# BladeCore-M40.net
KiCad netlist of a schematic drawn in EAGLE
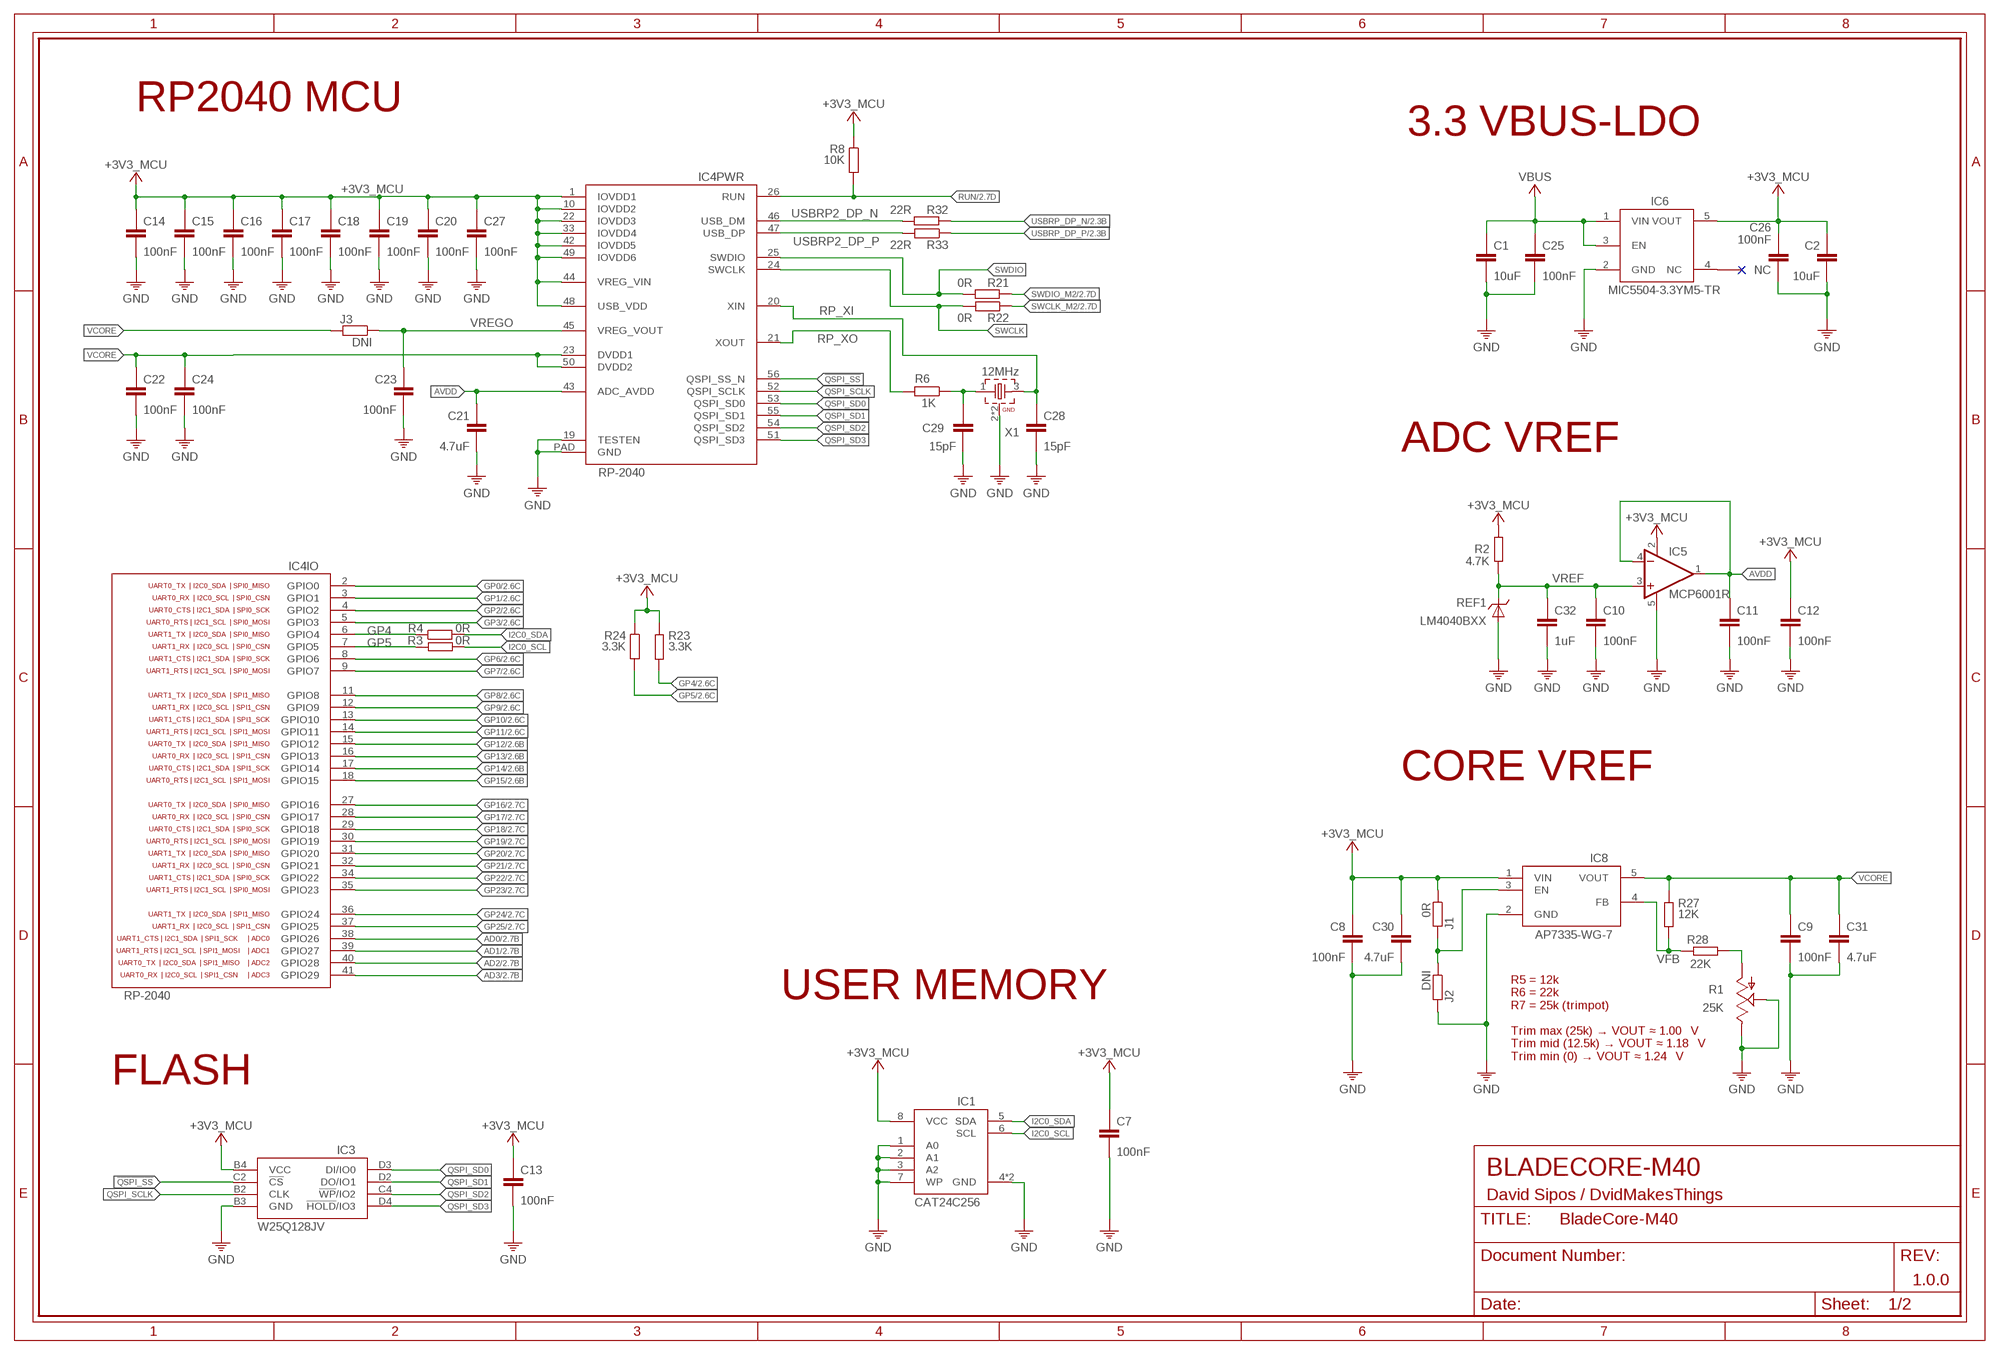
[diagram p0: schematic, sheet 1]
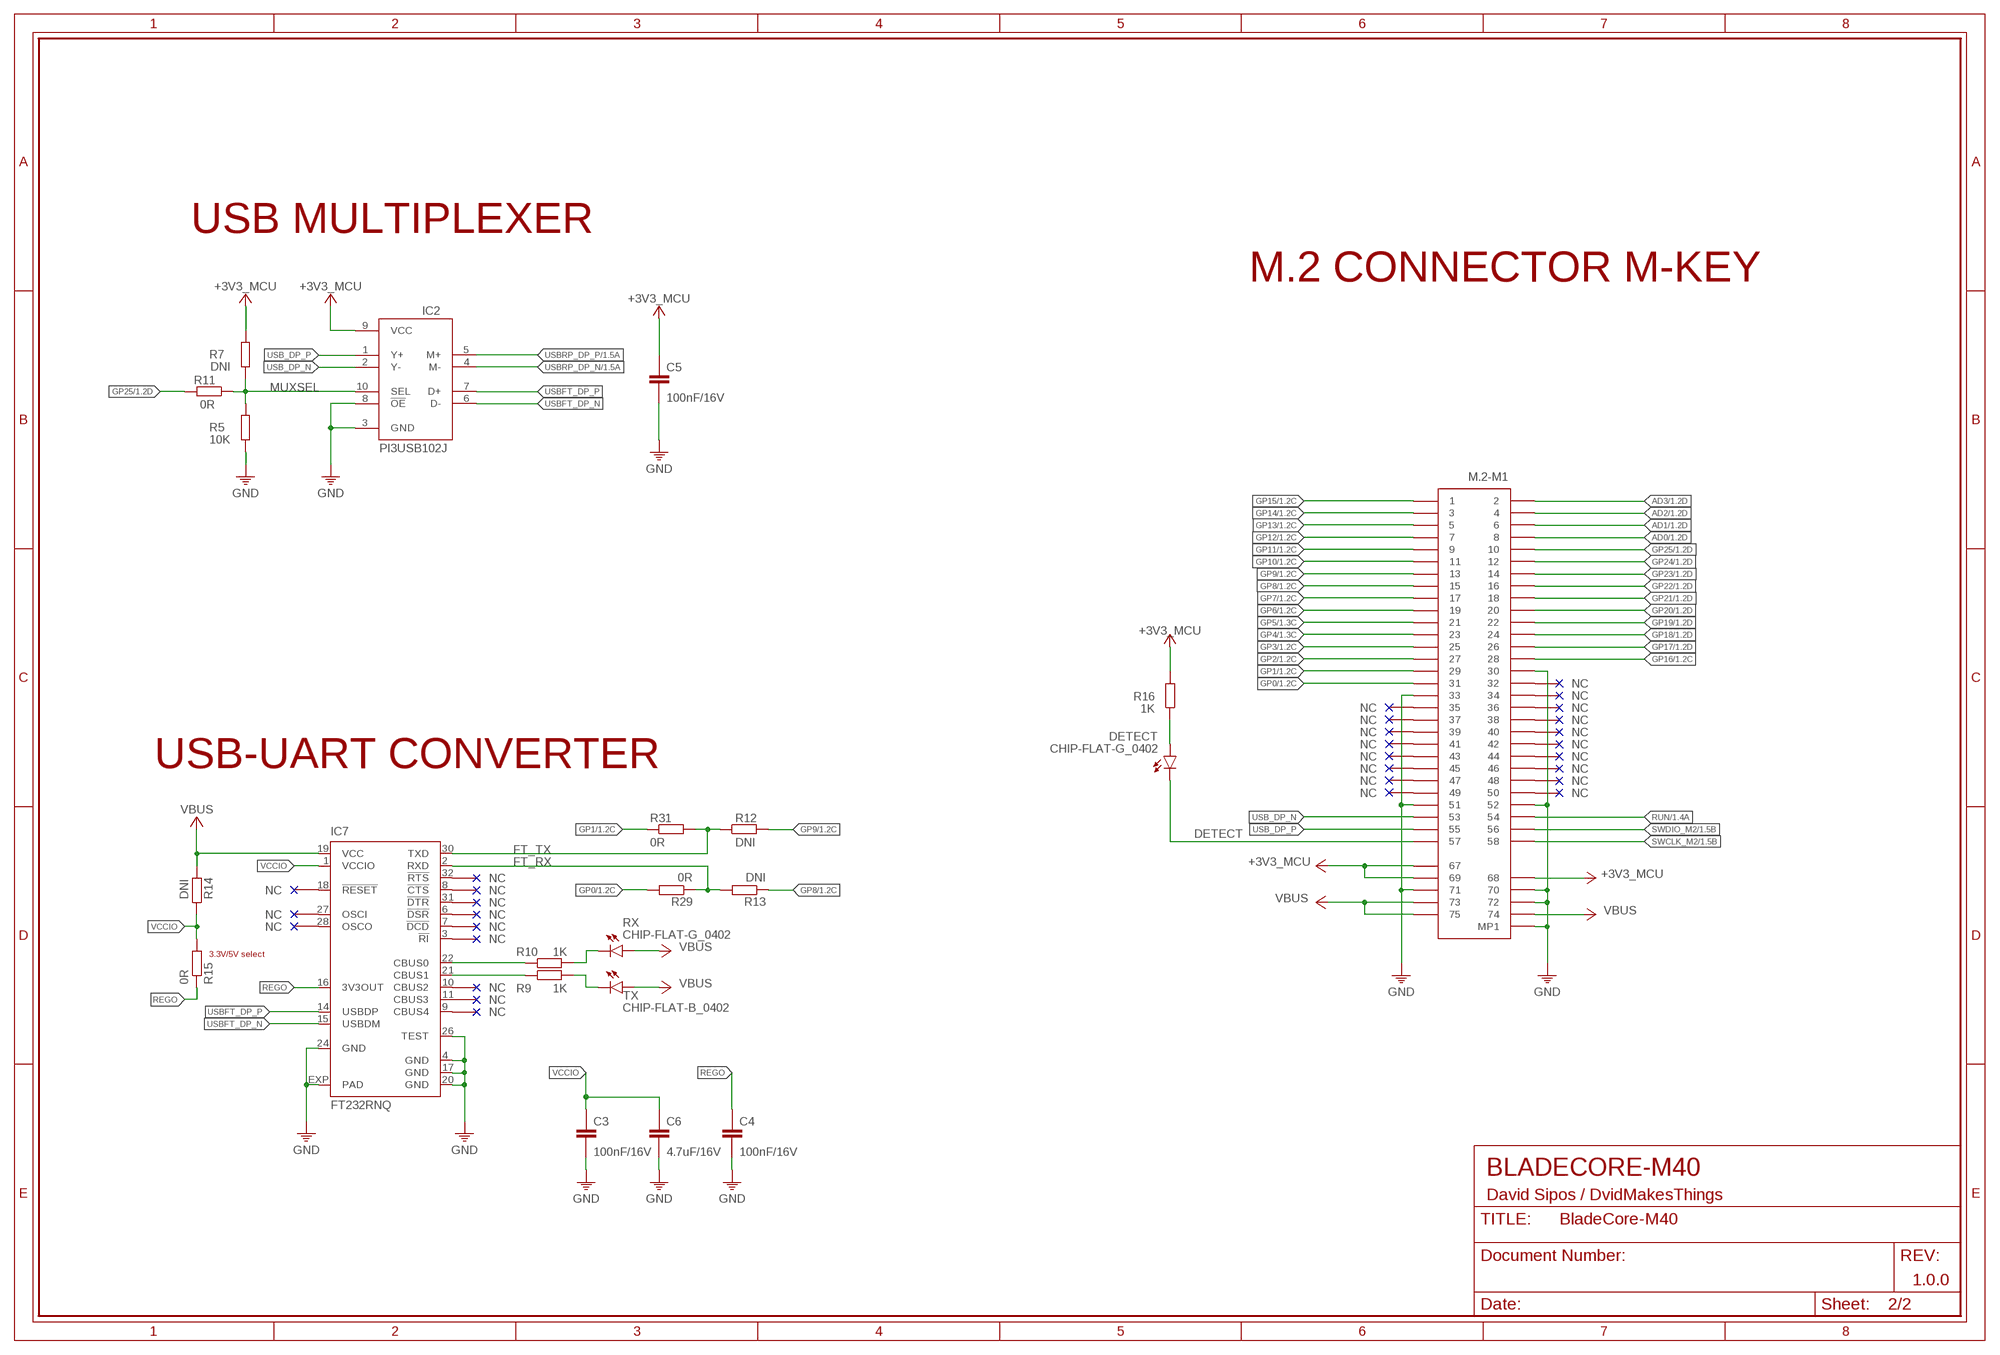
[diagram p1: schematic, sheet 2]

(export (version "E")
  (design (tool "Eeschema 10.0.6"))
  (components
    (comp (ref "C3")
      (value "100nF/16V")
      (footprint "eagle-import:0201")
      (libsource (lib "eagle-import") (part "C-0201"))
    )
    (comp (ref "C4")
      (value "100nF/16V")
      (footprint "eagle-import:0201")
      (libsource (lib "eagle-import") (part "C-0201"))
    )
    (comp (ref "C5")
      (value "100nF/16V")
      (footprint "eagle-import:0201")
      (libsource (lib "eagle-import") (part "C-0201"))
    )
    (comp (ref "C6")
      (value "4.7uF/16V")
      (footprint "eagle-import:0201")
      (libsource (lib "eagle-import") (part "C-0201"))
    )
    (comp (ref "DETECT")
      (value "CHIP-FLAT-G_0402")
      (footprint "eagle-import:LEDC1005X25N_FLAT-G")
      (libsource (lib "eagle-import") (part "CHIP-FLAT-G_0402"))
    )
    (comp (ref "IC2")
      (value "PI3USB102J")
      (footprint "eagle-import:QFN40P120X140X35-10N")
      (libsource (lib "eagle-import") (part "PI3USB102JXUCEX"))
    )
    (comp (ref "IC7")
      (value "FT232RNQ")
      (footprint "eagle-import:QFN32")
      (libsource (lib "eagle-import") (part "FT232RQ"))
    )
    (comp (ref "M.2-M1")
      (value "M.2-M-KEY")
      (footprint "eagle-import:M.2-M-KEY")
      (libsource (lib "eagle-import") (part "M.2-M-KEY"))
    )
    (comp (ref "R5")
      (value "10K")
      (footprint "eagle-import:R0201")
      (libsource (lib "eagle-import") (part "R0201"))
    )
    (comp (ref "R7")
      (value "DNI")
      (footprint "eagle-import:R0201")
      (libsource (lib "eagle-import") (part "R0201"))
    )
    (comp (ref "R9")
      (value "1K")
      (footprint "eagle-import:R0201")
      (libsource (lib "eagle-import") (part "R0201"))
    )
    (comp (ref "R10")
      (value "1K")
      (footprint "eagle-import:R0201")
      (libsource (lib "eagle-import") (part "R0201"))
    )
    (comp (ref "R11")
      (value "0R")
      (footprint "eagle-import:R0201")
      (libsource (lib "eagle-import") (part "R0201"))
    )
    (comp (ref "R12")
      (value "DNI")
      (footprint "eagle-import:R0201")
      (libsource (lib "eagle-import") (part "R0201"))
    )
    (comp (ref "R13")
      (value "DNI")
      (footprint "eagle-import:R0201")
      (libsource (lib "eagle-import") (part "R0201"))
    )
    (comp (ref "R14")
      (value "DNI")
      (footprint "eagle-import:R0201")
      (libsource (lib "eagle-import") (part "R0201"))
    )
    (comp (ref "R15")
      (value "0R")
      (footprint "eagle-import:R0201")
      (libsource (lib "eagle-import") (part "R0201"))
    )
    (comp (ref "R16")
      (value "1K")
      (footprint "eagle-import:R0201")
      (libsource (lib "eagle-import") (part "R0201"))
    )
    (comp (ref "R29")
      (value "0R")
      (footprint "eagle-import:R0201")
      (libsource (lib "eagle-import") (part "R0201"))
    )
    (comp (ref "R31")
      (value "0R")
      (footprint "eagle-import:R0201")
      (libsource (lib "eagle-import") (part "R0201"))
    )
    (comp (ref "RX")
      (value "CHIP-FLAT-G_0402")
      (footprint "eagle-import:LEDC1005X25N_FLAT-G")
      (libsource (lib "eagle-import") (part "CHIP-FLAT-G_0402"))
    )
    (comp (ref "TX")
      (value "CHIP-FLAT-B_0402")
      (footprint "eagle-import:LEDC1005X25N_FLAT-B")
      (libsource (lib "eagle-import") (part "CHIP-FLAT-B_0402"))
    )
    (comp (ref "C1")
      (value "10uF")
      (footprint "eagle-import:0805")
      (libsource (lib "eagle-import") (part "C0805"))
    )
    (comp (ref "C2")
      (value "10uF")
      (footprint "eagle-import:0805")
      (libsource (lib "eagle-import") (part "C0805"))
    )
    (comp (ref "C7")
      (value "100nF")
      (footprint "eagle-import:0201")
      (libsource (lib "eagle-import") (part "C-0201"))
    )
    (comp (ref "C8")
      (value "100nF")
      (footprint "eagle-import:0201")
      (libsource (lib "eagle-import") (part "C-0201"))
    )
    (comp (ref "C9")
      (value "100nF")
      (footprint "eagle-import:0201")
      (libsource (lib "eagle-import") (part "C-0201"))
    )
    (comp (ref "C10")
      (value "100nF")
      (footprint "eagle-import:0201")
      (libsource (lib "eagle-import") (part "C-0201"))
    )
    (comp (ref "C11")
      (value "100nF")
      (footprint "eagle-import:0201")
      (libsource (lib "eagle-import") (part "C-0201"))
    )
    (comp (ref "C12")
      (value "100nF")
      (footprint "eagle-import:0201")
      (libsource (lib "eagle-import") (part "C-0201"))
    )
    (comp (ref "C13")
      (value "100nF")
      (footprint "eagle-import:0201")
      (libsource (lib "eagle-import") (part "C-0201"))
    )
    (comp (ref "C14")
      (value "100nF")
      (footprint "eagle-import:0201")
      (libsource (lib "eagle-import") (part "C-0201"))
    )
    (comp (ref "C15")
      (value "100nF")
      (footprint "eagle-import:0201")
      (libsource (lib "eagle-import") (part "C-0201"))
    )
    (comp (ref "C16")
      (value "100nF")
      (footprint "eagle-import:0201")
      (libsource (lib "eagle-import") (part "C-0201"))
    )
    (comp (ref "C17")
      (value "100nF")
      (footprint "eagle-import:0201")
      (libsource (lib "eagle-import") (part "C-0201"))
    )
    (comp (ref "C18")
      (value "100nF")
      (footprint "eagle-import:0201")
      (libsource (lib "eagle-import") (part "C-0201"))
    )
    (comp (ref "C19")
      (value "100nF")
      (footprint "eagle-import:0201")
      (libsource (lib "eagle-import") (part "C-0201"))
    )
    (comp (ref "C20")
      (value "100nF")
      (footprint "eagle-import:0201")
      (libsource (lib "eagle-import") (part "C-0201"))
    )
    (comp (ref "C21")
      (value "4.7uF")
      (footprint "eagle-import:C0402")
      (libsource (lib "eagle-import") (part "C-0402"))
    )
    (comp (ref "C22")
      (value "100nF")
      (footprint "eagle-import:0201")
      (libsource (lib "eagle-import") (part "C-0201"))
    )
    (comp (ref "C23")
      (value "100nF")
      (footprint "eagle-import:0201")
      (libsource (lib "eagle-import") (part "C-0201"))
    )
    (comp (ref "C24")
      (value "100nF")
      (footprint "eagle-import:0201")
      (libsource (lib "eagle-import") (part "C-0201"))
    )
    (comp (ref "C25")
      (value "100nF")
      (footprint "eagle-import:0201")
      (libsource (lib "eagle-import") (part "C-0201"))
    )
    (comp (ref "C26")
      (value "100nF")
      (footprint "eagle-import:0201")
      (libsource (lib "eagle-import") (part "C-0201"))
    )
    (comp (ref "C27")
      (value "100nF")
      (footprint "eagle-import:0201")
      (libsource (lib "eagle-import") (part "C-0201"))
    )
    (comp (ref "C28")
      (value "15pF")
      (footprint "eagle-import:0201")
      (libsource (lib "eagle-import") (part "C-0201"))
    )
    (comp (ref "C29")
      (value "15pF")
      (footprint "eagle-import:0201")
      (libsource (lib "eagle-import") (part "C-0201"))
    )
    (comp (ref "C30")
      (value "4.7uF")
      (footprint "eagle-import:C0402")
      (libsource (lib "eagle-import") (part "C-0402"))
    )
    (comp (ref "C31")
      (value "4.7uF")
      (footprint "eagle-import:C0402")
      (libsource (lib "eagle-import") (part "C-0402"))
    )
    (comp (ref "C32")
      (value "1uF")
      (footprint "eagle-import:C0402")
      (libsource (lib "eagle-import") (part "C-0402"))
    )
    (comp (ref "IC1")
      (value "CAT24C512HU5IGT3")
      (footprint "eagle-import:SON50P300X200X50-9T130X140N")
      (libsource (lib "eagle-import") (part "CAT24C256-HU4"))
    )
    (comp (ref "IC3")
      (value "W25Q128JVCIQ TR")
      (footprint "eagle-import:BGA24C100P4X6_800X600X120N")
      (libsource (lib "eagle-import") (part "W25Q128JVC"))
    )
    (comp (ref "IC4")
      (value "RP-2040")
      (footprint "eagle-import:QFN56")
      (libsource (lib "eagle-import") (part "RP-2040"))
    )
    (comp (ref "IC5")
      (value "MCP6001R")
      (footprint "eagle-import:SOT23-5")
      (libsource (lib "eagle-import") (part "MCP6001RT"))
    )
    (comp (ref "IC6")
      (value "MIC5504-3.3YM5-TR")
      (footprint "eagle-import:SOT23-5")
      (libsource (lib "eagle-import") (part "MIC5504-3.3YM5-TR"))
    )
    (comp (ref "IC8")
      (value "AP7335-WG-7")
      (footprint "eagle-import:SOT23-5")
      (libsource (lib "eagle-import") (part "AP7335-WG-7"))
    )
    (comp (ref "J1")
      (value "0R")
      (footprint "eagle-import:R0201")
      (libsource (lib "eagle-import") (part "R0201"))
    )
    (comp (ref "J2")
      (value "DNI")
      (footprint "eagle-import:R0201")
      (libsource (lib "eagle-import") (part "R0201"))
    )
    (comp (ref "J3")
      (value "DNI")
      (footprint "eagle-import:R0201")
      (libsource (lib "eagle-import") (part "R0201"))
    )
    (comp (ref "R1")
      (value "25K")
      (footprint "eagle-import:SMD_TRIMMER")
      (fields
        (field (name "DIGIKEY_PART_NUMBER") "987-1694-2-ND")
        (field (name "MANUFACTURER") "TT Electronics/BI")
        (field (name "MPN") "35WR10KLFTR")
        (field (name "CREATED_BY") "PCBLayout.com")
      )
      (libsource (lib "eagle-import") (part "35WR10KLFTR"))
    )
    (comp (ref "R2")
      (value "4.7K")
      (footprint "eagle-import:R0201")
      (libsource (lib "eagle-import") (part "R0201"))
    )
    (comp (ref "R3")
      (value "0R")
      (footprint "eagle-import:R0201")
      (libsource (lib "eagle-import") (part "R0201"))
    )
    (comp (ref "R4")
      (value "0R")
      (footprint "eagle-import:R0201")
      (libsource (lib "eagle-import") (part "R0201"))
    )
    (comp (ref "R6")
      (value "1K")
      (footprint "eagle-import:R0201")
      (libsource (lib "eagle-import") (part "R0201"))
    )
    (comp (ref "R8")
      (value "10K")
      (footprint "eagle-import:R0201")
      (libsource (lib "eagle-import") (part "R0201"))
    )
    (comp (ref "R21")
      (value "0R")
      (footprint "eagle-import:R0201")
      (libsource (lib "eagle-import") (part "R0201"))
    )
    (comp (ref "R22")
      (value "0R")
      (footprint "eagle-import:R0201")
      (libsource (lib "eagle-import") (part "R0201"))
    )
    (comp (ref "R23")
      (value "3.3K")
      (footprint "eagle-import:R0201")
      (libsource (lib "eagle-import") (part "R0201"))
    )
    (comp (ref "R24")
      (value "3.3K")
      (footprint "eagle-import:R0201")
      (libsource (lib "eagle-import") (part "R0201"))
    )
    (comp (ref "R27")
      (value "12K")
      (footprint "eagle-import:R0201")
      (libsource (lib "eagle-import") (part "R0201"))
    )
    (comp (ref "R28")
      (value "22K")
      (footprint "eagle-import:R0201")
      (libsource (lib "eagle-import") (part "R0201"))
    )
    (comp (ref "R32")
      (value "22R")
      (footprint "eagle-import:R0201")
      (libsource (lib "eagle-import") (part "R0201"))
    )
    (comp (ref "R33")
      (value "22R")
      (footprint "eagle-import:R0201")
      (libsource (lib "eagle-import") (part "R0201"))
    )
    (comp (ref "REF1")
      (value "LM4040BXX")
      (footprint "eagle-import:SOT23")
      (libsource (lib "eagle-import") (part "LM4040BXX"))
    )
    (comp (ref "X1")
      (value "12MHz")
      (footprint "eagle-import:WE-XTAL_CFPX-180")
      (fields (field (name "TOLERANCE") "±20ppm"))
      (libsource (lib "eagle-import") (part "WE-XTAL_CFPX-180_830069944"))
    )
  )
  (nets
    (net (code "1") (name "+3V3_MCU") (class "Default")
      (node (ref "C12") (pin "1") (pinfunction "1_1") (pintype "passive"))
      (node (ref "C13") (pin "1") (pinfunction "1_1") (pintype "passive"))
      (node (ref "C14") (pin "1") (pinfunction "1_1") (pintype "passive"))
      (node (ref "C15") (pin "1") (pinfunction "1_1") (pintype "passive"))
      (node (ref "C16") (pin "1") (pinfunction "1_1") (pintype "passive"))
      (node (ref "C17") (pin "1") (pinfunction "1_1") (pintype "passive"))
      (node (ref "C18") (pin "1") (pinfunction "1_1") (pintype "passive"))
      (node (ref "C19") (pin "1") (pinfunction "1_1") (pintype "passive"))
      (node (ref "C2") (pin "1") (pinfunction "1_1") (pintype "passive"))
      (node (ref "C20") (pin "1") (pinfunction "1_1") (pintype "passive"))
      (node (ref "C26") (pin "1") (pinfunction "1_1") (pintype "passive"))
      (node (ref "C27") (pin "1") (pinfunction "1_1") (pintype "passive"))
      (node (ref "C30") (pin "1") (pinfunction "1_1") (pintype "passive"))
      (node (ref "C5") (pin "1") (pinfunction "1_1") (pintype "passive"))
      (node (ref "C7") (pin "1") (pinfunction "1_1") (pintype "passive"))
      (node (ref "C8") (pin "1") (pinfunction "1_1") (pintype "passive"))
      (node (ref "IC1") (pin "8") (pinfunction "VCC_8") (pintype "power_in"))
      (node (ref "IC2") (pin "9") (pinfunction "VCC_9") (pintype "power_in"))
      (node (ref "IC3") (pin "B4") (pinfunction "VCC_B4") (pintype "power_in"))
      (node (ref "IC4") (pin "1") (pinfunction "IOVDD1_1") (pintype "power_in"))
      (node (ref "IC4") (pin "10") (pinfunction "IOVDD2_10") (pintype "power_in"))
      (node (ref "IC4") (pin "22") (pinfunction "IOVDD3_22") (pintype "power_in"))
      (node (ref "IC4") (pin "33") (pinfunction "IOVDD4_33") (pintype "power_in"))
      (node (ref "IC4") (pin "42") (pinfunction "IOVDD5_42") (pintype "power_in"))
      (node (ref "IC4") (pin "44") (pinfunction "VREG_VIN_44") (pintype "power_in"))
      (node (ref "IC4") (pin "48") (pinfunction "USB_VDD_48") (pintype "power_in"))
      (node (ref "IC4") (pin "49") (pinfunction "IOVDD6_49") (pintype "power_in"))
      (node (ref "IC5") (pin "2") (pinfunction "V+_2") (pintype "power_in"))
      (node (ref "IC6") (pin "5") (pinfunction "VOUT_5") (pintype "bidirectional"))
      (node (ref "IC8") (pin "1") (pinfunction "VIN_1") (pintype "power_in"))
      (node (ref "J1") (pin "1") (pinfunction "1_1") (pintype "passive"))
      (node (ref "M.2-M1") (pin "P$67") (pinfunction "67_P$67") (pintype "bidirectional"))
      (node (ref "M.2-M1") (pin "P$68") (pinfunction "68_P$68") (pintype "bidirectional"))
      (node (ref "M.2-M1") (pin "P$69") (pinfunction "69_P$69") (pintype "bidirectional"))
      (node (ref "R16") (pin "2") (pinfunction "2_2") (pintype "passive"))
      (node (ref "R2") (pin "2") (pinfunction "2_2") (pintype "passive"))
      (node (ref "R23") (pin "1") (pinfunction "1_1") (pintype "passive"))
      (node (ref "R24") (pin "1") (pinfunction "1_1") (pintype "passive"))
      (node (ref "R7") (pin "2") (pinfunction "2_2") (pintype "passive"))
      (node (ref "R8") (pin "1") (pinfunction "1_1") (pintype "passive"))
    )
    (net (code "2") (name "AD0") (class "Default")
      (node (ref "IC4") (pin "38") (pinfunction "GPIO26_38") (pintype "bidirectional"))
      (node (ref "M.2-M1") (pin "P$8") (pinfunction "8_P$8") (pintype "bidirectional"))
    )
    (net (code "3") (name "AD1") (class "Default")
      (node (ref "IC4") (pin "39") (pinfunction "GPIO27_39") (pintype "bidirectional"))
      (node (ref "M.2-M1") (pin "P$6") (pinfunction "6_P$6") (pintype "bidirectional"))
    )
    (net (code "4") (name "AD2") (class "Default")
      (node (ref "IC4") (pin "40") (pinfunction "GPIO28_40") (pintype "bidirectional"))
      (node (ref "M.2-M1") (pin "P$4") (pinfunction "4_P$4") (pintype "bidirectional"))
    )
    (net (code "5") (name "AD3") (class "Default")
      (node (ref "IC4") (pin "41") (pinfunction "GPIO29_41") (pintype "bidirectional"))
      (node (ref "M.2-M1") (pin "P$2") (pinfunction "2_P$2") (pintype "bidirectional"))
    )
    (net (code "6") (name "AVDD") (class "Default")
      (node (ref "C11") (pin "1") (pinfunction "1_1") (pintype "passive"))
      (node (ref "C21") (pin "1") (pinfunction "1_1") (pintype "passive"))
      (node (ref "IC4") (pin "43") (pinfunction "ADC_AVDD_43") (pintype "power_in"))
      (node (ref "IC5") (pin "1") (pinfunction "OUT_1") (pintype "output"))
      (node (ref "IC5") (pin "4") (pinfunction "-IN_4") (pintype "input"))
    )
    (net (code "7") (name "DETECT") (class "Default")
      (node (ref "DETECT") (pin "C") (pinfunction "C_C") (pintype "passive"))
      (node (ref "M.2-M1") (pin "P$57") (pinfunction "57_P$57") (pintype "bidirectional"))
    )
    (net (code "8") (name "FT_RX") (class "Default")
      (node (ref "IC7") (pin "2") (pinfunction "RXD_2") (pintype "input"))
      (node (ref "R13") (pin "2") (pinfunction "2_2") (pintype "passive"))
      (node (ref "R29") (pin "1") (pinfunction "1_1") (pintype "passive"))
    )
    (net (code "9") (name "FT_TX") (class "Default")
      (node (ref "IC7") (pin "30") (pinfunction "TXD_30") (pintype "output"))
      (node (ref "R12") (pin "1") (pinfunction "1_1") (pintype "passive"))
      (node (ref "R31") (pin "2") (pinfunction "2_2") (pintype "passive"))
    )
    (net (code "10") (name "GND") (class "Default")
      (node (ref "C1") (pin "2") (pinfunction "2_2") (pintype "passive"))
      (node (ref "C10") (pin "2") (pinfunction "2_2") (pintype "passive"))
      (node (ref "C11") (pin "2") (pinfunction "2_2") (pintype "passive"))
      (node (ref "C12") (pin "2") (pinfunction "2_2") (pintype "passive"))
      (node (ref "C13") (pin "2") (pinfunction "2_2") (pintype "passive"))
      (node (ref "C14") (pin "2") (pinfunction "2_2") (pintype "passive"))
      (node (ref "C15") (pin "2") (pinfunction "2_2") (pintype "passive"))
      (node (ref "C16") (pin "2") (pinfunction "2_2") (pintype "passive"))
      (node (ref "C17") (pin "2") (pinfunction "2_2") (pintype "passive"))
      (node (ref "C18") (pin "2") (pinfunction "2_2") (pintype "passive"))
      (node (ref "C19") (pin "2") (pinfunction "2_2") (pintype "passive"))
      (node (ref "C2") (pin "2") (pinfunction "2_2") (pintype "passive"))
      (node (ref "C20") (pin "2") (pinfunction "2_2") (pintype "passive"))
      (node (ref "C21") (pin "2") (pinfunction "2_2") (pintype "passive"))
      (node (ref "C22") (pin "2") (pinfunction "2_2") (pintype "passive"))
      (node (ref "C23") (pin "2") (pinfunction "2_2") (pintype "passive"))
      (node (ref "C24") (pin "2") (pinfunction "2_2") (pintype "passive"))
      (node (ref "C25") (pin "2") (pinfunction "2_2") (pintype "passive"))
      (node (ref "C26") (pin "2") (pinfunction "2_2") (pintype "passive"))
      (node (ref "C27") (pin "2") (pinfunction "2_2") (pintype "passive"))
      (node (ref "C28") (pin "2") (pinfunction "2_2") (pintype "passive"))
      (node (ref "C29") (pin "2") (pinfunction "2_2") (pintype "passive"))
      (node (ref "C3") (pin "2") (pinfunction "2_2") (pintype "passive"))
      (node (ref "C30") (pin "2") (pinfunction "2_2") (pintype "passive"))
      (node (ref "C31") (pin "2") (pinfunction "2_2") (pintype "passive"))
      (node (ref "C32") (pin "2") (pinfunction "2_2") (pintype "passive"))
      (node (ref "C4") (pin "2") (pinfunction "2_2") (pintype "passive"))
      (node (ref "C5") (pin "2") (pinfunction "2_2") (pintype "passive"))
      (node (ref "C6") (pin "2") (pinfunction "2_2") (pintype "passive"))
      (node (ref "C7") (pin "2") (pinfunction "2_2") (pintype "passive"))
      (node (ref "C8") (pin "2") (pinfunction "2_2") (pintype "passive"))
      (node (ref "C9") (pin "2") (pinfunction "2_2") (pintype "passive"))
      (node (ref "IC1") (pin "1") (pinfunction "A0_1") (pintype "bidirectional"))
      (node (ref "IC1") (pin "2") (pinfunction "A1_2") (pintype "bidirectional"))
      (node (ref "IC1") (pin "3") (pinfunction "A2_3") (pintype "bidirectional"))
      (node (ref "IC1") (pin "4") (pinfunction "GND_4") (pintype "power_in"))
      (node (ref "IC1") (pin "7") (pinfunction "WP_7") (pintype "bidirectional"))
      (node (ref "IC1") (pin "9") (pinfunction "GND_9") (pintype "power_in"))
      (node (ref "IC2") (pin "3") (pinfunction "GND_3") (pintype "power_in"))
      (node (ref "IC2") (pin "8") (pinfunction "~{OE}_8") (pintype "input"))
      (node (ref "IC3") (pin "B3") (pinfunction "GND_B3") (pintype "power_in"))
      (node (ref "IC4") (pin "19") (pinfunction "TESTEN_19") (pintype "bidirectional"))
      (node (ref "IC4") (pin "PAD") (pinfunction "GND_PAD") (pintype "power_in"))
      (node (ref "IC5") (pin "5") (pinfunction "V-_5") (pintype "power_in"))
      (node (ref "IC6") (pin "2") (pinfunction "GND_2") (pintype "bidirectional"))
      (node (ref "IC7") (pin "17") (pinfunction "GND_17") (pintype "power_in"))
      (node (ref "IC7") (pin "20") (pinfunction "GND_20") (pintype "power_in"))
      (node (ref "IC7") (pin "24") (pinfunction "GND_24") (pintype "power_in"))
      (node (ref "IC7") (pin "26") (pinfunction "TEST_26") (pintype "input"))
      (node (ref "IC7") (pin "4") (pinfunction "GND_4") (pintype "power_in"))
      (node (ref "IC7") (pin "EXP") (pinfunction "PAD_EXP") (pintype "power_in"))
      (node (ref "IC8") (pin "2") (pinfunction "GND_2") (pintype "power_in"))
      (node (ref "J2") (pin "2") (pinfunction "2_2") (pintype "passive"))
      (node (ref "M.2-M1") (pin "MT1") (pinfunction "MP1_MT1") (pintype "bidirectional"))
      (node (ref "M.2-M1") (pin "P$30") (pinfunction "30_P$30") (pintype "bidirectional"))
      (node (ref "M.2-M1") (pin "P$33") (pinfunction "33_P$33") (pintype "bidirectional"))
      (node (ref "M.2-M1") (pin "P$51") (pinfunction "51_P$51") (pintype "bidirectional"))
      (node (ref "M.2-M1") (pin "P$52") (pinfunction "52_P$52") (pintype "bidirectional"))
      (node (ref "M.2-M1") (pin "P$70") (pinfunction "70_P$70") (pintype "bidirectional"))
      (node (ref "M.2-M1") (pin "P$71") (pinfunction "71_P$71") (pintype "bidirectional"))
      (node (ref "M.2-M1") (pin "P$72") (pinfunction "72_P$72") (pintype "bidirectional"))
      (node (ref "R1") (pin "1") (pinfunction "1_1") (pintype "passive"))
      (node (ref "R1") (pin "2") (pinfunction "2_2") (pintype "passive"))
      (node (ref "R5") (pin "1") (pinfunction "1_1") (pintype "passive"))
      (node (ref "REF1") (pin "2") (pinfunction "A_2") (pintype "passive"))
      (node (ref "REF1") (pin "3") (pinfunction "A_3") (pintype "passive"))
      (node (ref "X1") (pin "2") (pinfunction "GND_2") (pintype "passive"))
      (node (ref "X1") (pin "4") (pinfunction "GND_4") (pintype "passive"))
    )
    (net (code "11") (name "GP0") (class "Default")
      (node (ref "IC4") (pin "2") (pinfunction "GPIO0_2") (pintype "bidirectional"))
      (node (ref "M.2-M1") (pin "P$31") (pinfunction "31_P$31") (pintype "bidirectional"))
      (node (ref "R29") (pin "2") (pinfunction "2_2") (pintype "passive"))
    )
    (net (code "12") (name "GP1") (class "Default")
      (node (ref "IC4") (pin "3") (pinfunction "GPIO1_3") (pintype "bidirectional"))
      (node (ref "M.2-M1") (pin "P$29") (pinfunction "29_P$29") (pintype "bidirectional"))
      (node (ref "R31") (pin "1") (pinfunction "1_1") (pintype "passive"))
    )
    (net (code "13") (name "GP2") (class "Default")
      (node (ref "IC4") (pin "4") (pinfunction "GPIO2_4") (pintype "bidirectional"))
      (node (ref "M.2-M1") (pin "P$27") (pinfunction "27_P$27") (pintype "bidirectional"))
    )
    (net (code "14") (name "GP3") (class "Default")
      (node (ref "IC4") (pin "5") (pinfunction "GPIO3_5") (pintype "bidirectional"))
      (node (ref "M.2-M1") (pin "P$25") (pinfunction "25_P$25") (pintype "bidirectional"))
    )
    (net (code "15") (name "GP4") (class "Default")
      (node (ref "IC4") (pin "6") (pinfunction "GPIO4_6") (pintype "bidirectional"))
      (node (ref "M.2-M1") (pin "P$23") (pinfunction "23_P$23") (pintype "bidirectional"))
      (node (ref "R23") (pin "2") (pinfunction "2_2") (pintype "passive"))
      (node (ref "R4") (pin "1") (pinfunction "1_1") (pintype "passive"))
    )
    (net (code "16") (name "GP5") (class "Default")
      (node (ref "IC4") (pin "7") (pinfunction "GPIO5_7") (pintype "bidirectional"))
      (node (ref "M.2-M1") (pin "P$21") (pinfunction "21_P$21") (pintype "bidirectional"))
      (node (ref "R24") (pin "2") (pinfunction "2_2") (pintype "passive"))
      (node (ref "R3") (pin "1") (pinfunction "1_1") (pintype "passive"))
    )
    (net (code "17") (name "GP6") (class "Default")
      (node (ref "IC4") (pin "8") (pinfunction "GPIO6_8") (pintype "bidirectional"))
      (node (ref "M.2-M1") (pin "P$19") (pinfunction "19_P$19") (pintype "bidirectional"))
    )
    (net (code "18") (name "GP7") (class "Default")
      (node (ref "IC4") (pin "9") (pinfunction "GPIO7_9") (pintype "bidirectional"))
      (node (ref "M.2-M1") (pin "P$17") (pinfunction "17_P$17") (pintype "bidirectional"))
    )
    (net (code "19") (name "GP8") (class "Default")
      (node (ref "IC4") (pin "11") (pinfunction "GPIO8_11") (pintype "bidirectional"))
      (node (ref "M.2-M1") (pin "P$15") (pinfunction "15_P$15") (pintype "bidirectional"))
      (node (ref "R13") (pin "1") (pinfunction "1_1") (pintype "passive"))
    )
    (net (code "20") (name "GP9") (class "Default")
      (node (ref "IC4") (pin "12") (pinfunction "GPIO9_12") (pintype "bidirectional"))
      (node (ref "M.2-M1") (pin "P$13") (pinfunction "13_P$13") (pintype "bidirectional"))
      (node (ref "R12") (pin "2") (pinfunction "2_2") (pintype "passive"))
    )
    (net (code "21") (name "GP10") (class "Default")
      (node (ref "IC4") (pin "13") (pinfunction "GPIO10_13") (pintype "bidirectional"))
      (node (ref "M.2-M1") (pin "P$11") (pinfunction "11_P$11") (pintype "bidirectional"))
    )
    (net (code "22") (name "GP11") (class "Default")
      (node (ref "IC4") (pin "14") (pinfunction "GPIO11_14") (pintype "bidirectional"))
      (node (ref "M.2-M1") (pin "P$9") (pinfunction "9_P$9") (pintype "bidirectional"))
    )
    (net (code "23") (name "GP12") (class "Default")
      (node (ref "IC4") (pin "15") (pinfunction "GPIO12_15") (pintype "bidirectional"))
      (node (ref "M.2-M1") (pin "P$7") (pinfunction "7_P$7") (pintype "bidirectional"))
    )
    (net (code "24") (name "GP13") (class "Default")
      (node (ref "IC4") (pin "16") (pinfunction "GPIO13_16") (pintype "bidirectional"))
      (node (ref "M.2-M1") (pin "P$5") (pinfunction "5_P$5") (pintype "bidirectional"))
    )
    (net (code "25") (name "GP14") (class "Default")
      (node (ref "IC4") (pin "17") (pinfunction "GPIO14_17") (pintype "bidirectional"))
      (node (ref "M.2-M1") (pin "P$3") (pinfunction "3_P$3") (pintype "bidirectional"))
    )
    (net (code "26") (name "GP15") (class "Default")
      (node (ref "IC4") (pin "18") (pinfunction "GPIO15_18") (pintype "bidirectional"))
      (node (ref "M.2-M1") (pin "P$1") (pinfunction "1_P$1") (pintype "bidirectional"))
    )
    (net (code "27") (name "GP16") (class "Default")
      (node (ref "IC4") (pin "27") (pinfunction "GPIO16_27") (pintype "bidirectional"))
      (node (ref "M.2-M1") (pin "P$28") (pinfunction "28_P$28") (pintype "bidirectional"))
    )
    (net (code "28") (name "GP17") (class "Default")
      (node (ref "IC4") (pin "28") (pinfunction "GPIO17_28") (pintype "bidirectional"))
      (node (ref "M.2-M1") (pin "P$26") (pinfunction "26_P$26") (pintype "bidirectional"))
    )
    (net (code "29") (name "GP18") (class "Default")
      (node (ref "IC4") (pin "29") (pinfunction "GPIO18_29") (pintype "bidirectional"))
      (node (ref "M.2-M1") (pin "P$24") (pinfunction "24_P$24") (pintype "bidirectional"))
    )
    (net (code "30") (name "GP19") (class "Default")
      (node (ref "IC4") (pin "30") (pinfunction "GPIO19_30") (pintype "bidirectional"))
      (node (ref "M.2-M1") (pin "P$22") (pinfunction "22_P$22") (pintype "bidirectional"))
    )
    (net (code "31") (name "GP20") (class "Default")
      (node (ref "IC4") (pin "31") (pinfunction "GPIO20_31") (pintype "bidirectional"))
      (node (ref "M.2-M1") (pin "P$20") (pinfunction "20_P$20") (pintype "bidirectional"))
    )
    (net (code "32") (name "GP21") (class "Default")
      (node (ref "IC4") (pin "32") (pinfunction "GPIO21_32") (pintype "bidirectional"))
      (node (ref "M.2-M1") (pin "P$18") (pinfunction "18_P$18") (pintype "bidirectional"))
    )
    (net (code "33") (name "GP22") (class "Default")
      (node (ref "IC4") (pin "34") (pinfunction "GPIO22_34") (pintype "bidirectional"))
      (node (ref "M.2-M1") (pin "P$16") (pinfunction "16_P$16") (pintype "bidirectional"))
    )
    (net (code "34") (name "GP23") (class "Default")
      (node (ref "IC4") (pin "35") (pinfunction "GPIO23_35") (pintype "bidirectional"))
      (node (ref "M.2-M1") (pin "P$14") (pinfunction "14_P$14") (pintype "bidirectional"))
    )
    (net (code "35") (name "GP24") (class "Default")
      (node (ref "IC4") (pin "36") (pinfunction "GPIO24_36") (pintype "bidirectional"))
      (node (ref "M.2-M1") (pin "P$12") (pinfunction "12_P$12") (pintype "bidirectional"))
    )
    (net (code "36") (name "GP25") (class "Default")
      (node (ref "IC4") (pin "37") (pinfunction "GPIO25_37") (pintype "bidirectional"))
      (node (ref "M.2-M1") (pin "P$10") (pinfunction "10_P$10") (pintype "bidirectional"))
      (node (ref "R11") (pin "2") (pinfunction "2_2") (pintype "passive"))
    )
    (net (code "37") (name "I2C0_SCL") (class "Default")
      (node (ref "IC1") (pin "6") (pinfunction "SCL_6") (pintype "bidirectional"))
      (node (ref "R3") (pin "2") (pinfunction "2_2") (pintype "passive"))
    )
    (net (code "38") (name "I2C0_SDA") (class "Default")
      (node (ref "IC1") (pin "5") (pinfunction "SDA_5") (pintype "bidirectional"))
      (node (ref "R4") (pin "2") (pinfunction "2_2") (pintype "passive"))
    )
    (net (code "39") (name "MUXSEL") (class "Default")
      (node (ref "IC2") (pin "10") (pinfunction "SEL_10") (pintype "input"))
      (node (ref "R11") (pin "1") (pinfunction "1_1") (pintype "passive"))
      (node (ref "R5") (pin "2") (pinfunction "2_2") (pintype "passive"))
      (node (ref "R7") (pin "1") (pinfunction "1_1") (pintype "passive"))
    )
    (net (code "40") (name "Net-(C29-Pad1)") (class "Default")
      (node (ref "C29") (pin "1") (pinfunction "1_1") (pintype "passive"))
      (node (ref "R6") (pin "1") (pinfunction "1_1") (pintype "passive"))
      (node (ref "X1") (pin "1") (pinfunction "1_1") (pintype "passive"))
    )
    (net (code "41") (name "Net-(DETECT-PadA)") (class "Default")
      (node (ref "DETECT") (pin "A") (pinfunction "A_A") (pintype "passive"))
      (node (ref "R16") (pin "1") (pinfunction "1_1") (pintype "passive"))
    )
    (net (code "42") (name "Net-(IC7-CBUS0)") (class "Default")
      (node (ref "IC7") (pin "22") (pinfunction "CBUS0_22") (pintype "bidirectional"))
      (node (ref "R10") (pin "1") (pinfunction "1_1") (pintype "passive"))
    )
    (net (code "43") (name "Net-(IC7-CBUS1)") (class "Default")
      (node (ref "IC7") (pin "21") (pinfunction "CBUS1_21") (pintype "bidirectional"))
      (node (ref "R9") (pin "1") (pinfunction "1_1") (pintype "passive"))
    )
    (net (code "44") (name "Net-(IC8-EN)") (class "Default")
      (node (ref "IC8") (pin "3") (pinfunction "EN_3") (pintype "input"))
      (node (ref "J1") (pin "2") (pinfunction "2_2") (pintype "passive"))
      (node (ref "J2") (pin "1") (pinfunction "1_1") (pintype "passive"))
    )
    (net (code "45") (name "Net-(R1-Pad3)") (class "Default")
      (node (ref "R1") (pin "3") (pinfunction "3_3") (pintype "passive"))
      (node (ref "R28") (pin "2") (pinfunction "2_2") (pintype "passive"))
    )
    (net (code "46") (name "Net-(R9-Pad2)") (class "Default")
      (node (ref "R9") (pin "2") (pinfunction "2_2") (pintype "passive"))
      (node (ref "TX") (pin "C") (pinfunction "C_C") (pintype "passive"))
    )
    (net (code "47") (name "Net-(R10-Pad2)") (class "Default")
      (node (ref "R10") (pin "2") (pinfunction "2_2") (pintype "passive"))
      (node (ref "RX") (pin "C") (pinfunction "C_C") (pintype "passive"))
    )
    (net (code "48") (name "QSPI_SCLK") (class "Default")
      (node (ref "IC3") (pin "B2") (pinfunction "CLK_B2") (pintype "bidirectional"))
      (node (ref "IC4") (pin "52") (pinfunction "QSPI_SCLK_52") (pintype "bidirectional"))
    )
    (net (code "49") (name "QSPI_SD0") (class "Default")
      (node (ref "IC3") (pin "D3") (pinfunction "DI/IO0_D3") (pintype "bidirectional"))
      (node (ref "IC4") (pin "53") (pinfunction "QSPI_SD0_53") (pintype "bidirectional"))
    )
    (net (code "50") (name "QSPI_SD1") (class "Default")
      (node (ref "IC3") (pin "D2") (pinfunction "DO/IO1_D2") (pintype "bidirectional"))
      (node (ref "IC4") (pin "55") (pinfunction "QSPI_SD1_55") (pintype "bidirectional"))
    )
    (net (code "51") (name "QSPI_SD2") (class "Default")
      (node (ref "IC3") (pin "C4") (pinfunction "~{WP}/IO2_C4") (pintype "bidirectional"))
      (node (ref "IC4") (pin "54") (pinfunction "QSPI_SD2_54") (pintype "bidirectional"))
    )
    (net (code "52") (name "QSPI_SD3") (class "Default")
      (node (ref "IC3") (pin "D4") (pinfunction "~{HOLD}/IO3_D4") (pintype "bidirectional"))
      (node (ref "IC4") (pin "51") (pinfunction "QSPI_SD3_51") (pintype "bidirectional"))
    )
    (net (code "53") (name "REGO") (class "Default")
      (node (ref "C4") (pin "1") (pinfunction "1_1") (pintype "passive"))
      (node (ref "IC7") (pin "16") (pinfunction "3V3OUT_16") (pintype "output"))
      (node (ref "R15") (pin "1") (pinfunction "1_1") (pintype "passive"))
    )
    (net (code "54") (name "RP_XI") (class "Default")
      (node (ref "C28") (pin "1") (pinfunction "1_1") (pintype "passive"))
      (node (ref "IC4") (pin "20") (pinfunction "XIN_20") (pintype "input"))
      (node (ref "X1") (pin "3") (pinfunction "2_3") (pintype "passive"))
    )
    (net (code "55") (name "RP_XO") (class "Default")
      (node (ref "IC4") (pin "21") (pinfunction "XOUT_21") (pintype "output"))
      (node (ref "R6") (pin "2") (pinfunction "2_2") (pintype "passive"))
    )
    (net (code "56") (name "RUN") (class "Default")
      (node (ref "IC4") (pin "26") (pinfunction "RUN_26") (pintype "input"))
      (node (ref "M.2-M1") (pin "P$54") (pinfunction "54_P$54") (pintype "bidirectional"))
      (node (ref "R8") (pin "2") (pinfunction "2_2") (pintype "passive"))
    )
    (net (code "57") (name "SWCLK") (class "Default")
      (node (ref "IC4") (pin "24") (pinfunction "SWCLK_24") (pintype "input"))
      (node (ref "R22") (pin "2") (pinfunction "2_2") (pintype "passive"))
    )
    (net (code "58") (name "SWCLK_M2") (class "Default")
      (node (ref "M.2-M1") (pin "P$58") (pinfunction "58_P$58") (pintype "bidirectional"))
      (node (ref "R22") (pin "1") (pinfunction "1_1") (pintype "passive"))
    )
    (net (code "59") (name "SWDIO") (class "Default")
      (node (ref "IC4") (pin "25") (pinfunction "SWDIO_25") (pintype "bidirectional"))
      (node (ref "R21") (pin "2") (pinfunction "2_2") (pintype "passive"))
    )
    (net (code "60") (name "SWDIO_M2") (class "Default")
      (node (ref "M.2-M1") (pin "P$56") (pinfunction "56_P$56") (pintype "bidirectional"))
      (node (ref "R21") (pin "1") (pinfunction "1_1") (pintype "passive"))
    )
    (net (code "61") (name "USBFT_DP_N") (class "Default")
      (node (ref "IC2") (pin "6") (pinfunction "D-_6") (pintype "bidirectional"))
      (node (ref "IC7") (pin "15") (pinfunction "USBDM_15") (pintype "bidirectional"))
    )
    (net (code "62") (name "USBFT_DP_P") (class "Default")
      (node (ref "IC2") (pin "7") (pinfunction "D+_7") (pintype "bidirectional"))
      (node (ref "IC7") (pin "14") (pinfunction "USBDP_14") (pintype "bidirectional"))
    )
    (net (code "63") (name "USBRP2_DP_N") (class "Default")
      (node (ref "IC4") (pin "46") (pinfunction "USB_DM_46") (pintype "bidirectional"))
      (node (ref "R32") (pin "2") (pinfunction "2_2") (pintype "passive"))
    )
    (net (code "64") (name "USBRP2_DP_P") (class "Default")
      (node (ref "IC4") (pin "47") (pinfunction "USB_DP_47") (pintype "bidirectional"))
      (node (ref "R33") (pin "2") (pinfunction "2_2") (pintype "passive"))
    )
    (net (code "65") (name "USBRP_DP_N") (class "Default")
      (node (ref "IC2") (pin "4") (pinfunction "M-_4") (pintype "bidirectional"))
      (node (ref "R32") (pin "1") (pinfunction "1_1") (pintype "passive"))
    )
    (net (code "66") (name "USBRP_DP_P") (class "Default")
      (node (ref "IC2") (pin "5") (pinfunction "M+_5") (pintype "bidirectional"))
      (node (ref "R33") (pin "1") (pinfunction "1_1") (pintype "passive"))
    )
    (net (code "67") (name "USB_DP_N") (class "Default")
      (node (ref "IC2") (pin "2") (pinfunction "Y-_2") (pintype "bidirectional"))
      (node (ref "M.2-M1") (pin "P$53") (pinfunction "53_P$53") (pintype "bidirectional"))
    )
    (net (code "68") (name "USB_DP_P") (class "Default")
      (node (ref "IC2") (pin "1") (pinfunction "Y+_1") (pintype "bidirectional"))
      (node (ref "M.2-M1") (pin "P$55") (pinfunction "55_P$55") (pintype "bidirectional"))
    )
    (net (code "69") (name "VBUS") (class "Default")
      (node (ref "C1") (pin "1") (pinfunction "1_1") (pintype "passive"))
      (node (ref "C25") (pin "1") (pinfunction "1_1") (pintype "passive"))
      (node (ref "IC6") (pin "1") (pinfunction "VIN_1") (pintype "bidirectional"))
      (node (ref "IC6") (pin "3") (pinfunction "EN_3") (pintype "bidirectional"))
      (node (ref "IC7") (pin "19") (pinfunction "VCC_19") (pintype "power_in"))
      (node (ref "M.2-M1") (pin "P$73") (pinfunction "73_P$73") (pintype "bidirectional"))
      (node (ref "M.2-M1") (pin "P$74") (pinfunction "74_P$74") (pintype "bidirectional"))
      (node (ref "M.2-M1") (pin "P$75") (pinfunction "75_P$75") (pintype "bidirectional"))
      (node (ref "R14") (pin "2") (pinfunction "2_2") (pintype "passive"))
      (node (ref "RX") (pin "A") (pinfunction "A_A") (pintype "passive"))
      (node (ref "TX") (pin "A") (pinfunction "A_A") (pintype "passive"))
    )
    (net (code "70") (name "VCCIO") (class "Default")
      (node (ref "C3") (pin "1") (pinfunction "1_1") (pintype "passive"))
      (node (ref "C6") (pin "1") (pinfunction "1_1") (pintype "passive"))
      (node (ref "IC7") (pin "1") (pinfunction "VCCIO_1") (pintype "power_in"))
      (node (ref "R14") (pin "1") (pinfunction "1_1") (pintype "passive"))
      (node (ref "R15") (pin "2") (pinfunction "2_2") (pintype "passive"))
    )
    (net (code "71") (name "VCORE") (class "Default")
      (node (ref "C22") (pin "1") (pinfunction "1_1") (pintype "passive"))
      (node (ref "C24") (pin "1") (pinfunction "1_1") (pintype "passive"))
      (node (ref "C31") (pin "1") (pinfunction "1_1") (pintype "passive"))
      (node (ref "C9") (pin "1") (pinfunction "1_1") (pintype "passive"))
      (node (ref "IC4") (pin "23") (pinfunction "DVDD1_23") (pintype "power_in"))
      (node (ref "IC4") (pin "50") (pinfunction "DVDD2_50") (pintype "power_in"))
      (node (ref "IC8") (pin "5") (pinfunction "VOUT_5") (pintype "power_in"))
      (node (ref "J3") (pin "2") (pinfunction "2_2") (pintype "passive"))
      (node (ref "R27") (pin "1") (pinfunction "1_1") (pintype "passive"))
    )
    (net (code "72") (name "VFB") (class "Default")
      (node (ref "IC8") (pin "4") (pinfunction "FB_4") (pintype "input"))
      (node (ref "R27") (pin "2") (pinfunction "2_2") (pintype "passive"))
      (node (ref "R28") (pin "1") (pinfunction "1_1") (pintype "passive"))
    )
    (net (code "73") (name "VREF") (class "Default")
      (node (ref "C10") (pin "1") (pinfunction "1_1") (pintype "passive"))
      (node (ref "C32") (pin "1") (pinfunction "1_1") (pintype "passive"))
      (node (ref "IC5") (pin "3") (pinfunction "+IN_3") (pintype "input"))
      (node (ref "R2") (pin "1") (pinfunction "1_1") (pintype "passive"))
      (node (ref "REF1") (pin "1") (pinfunction "C_1") (pintype "passive"))
    )
    (net (code "74") (name "VREGO") (class "Default")
      (node (ref "C23") (pin "1") (pinfunction "1_1") (pintype "passive"))
      (node (ref "IC4") (pin "45") (pinfunction "VREG_VOUT_45") (pintype "power_in"))
      (node (ref "J3") (pin "1") (pinfunction "1_1") (pintype "passive"))
    )
    (net (code "75") (name "unconnected-(IC6-NC-Pad4)") (class "Default")
      (node (ref "IC6") (pin "4") (pinfunction "NC_4") (pintype "bidirectional"))
    )
    (net (code "76") (name "unconnected-(IC7-CBUS2-Pad10)") (class "Default")
      (node (ref "IC7") (pin "10") (pinfunction "CBUS2_10") (pintype "bidirectional"))
    )
    (net (code "77") (name "unconnected-(IC7-CBUS3-Pad11)") (class "Default")
      (node (ref "IC7") (pin "11") (pinfunction "CBUS3_11") (pintype "bidirectional"))
    )
    (net (code "78") (name "unconnected-(IC7-CBUS4-Pad9)") (class "Default")
      (node (ref "IC7") (pin "9") (pinfunction "CBUS4_9") (pintype "bidirectional"))
    )
    (net (code "79") (name "unconnected-(IC7-OSCI-Pad27)") (class "Default")
      (node (ref "IC7") (pin "27") (pinfunction "OSCI_27") (pintype "input"))
    )
    (net (code "80") (name "unconnected-(IC7-OSCO-Pad28)") (class "Default")
      (node (ref "IC7") (pin "28") (pinfunction "OSCO_28") (pintype "output"))
    )
    (net (code "81") (name "unconnected-(IC7-~{CTS}-Pad8)") (class "Default")
      (node (ref "IC7") (pin "8") (pinfunction "~{CTS}_8") (pintype "input"))
    )
    (net (code "82") (name "unconnected-(IC7-~{DCD}-Pad7)") (class "Default")
      (node (ref "IC7") (pin "7") (pinfunction "~{DCD}_7") (pintype "input"))
    )
    (net (code "83") (name "unconnected-(IC7-~{DSR}-Pad6)") (class "Default")
      (node (ref "IC7") (pin "6") (pinfunction "~{DSR}_6") (pintype "input"))
    )
    (net (code "84") (name "unconnected-(IC7-~{DTR}-Pad31)") (class "Default")
      (node (ref "IC7") (pin "31") (pinfunction "~{DTR}_31") (pintype "output"))
    )
    (net (code "85") (name "unconnected-(IC7-~{RESET}-Pad18)") (class "Default")
      (node (ref "IC7") (pin "18") (pinfunction "~{RESET}_18") (pintype "input"))
    )
    (net (code "86") (name "unconnected-(IC7-~{RI}-Pad3)") (class "Default")
      (node (ref "IC7") (pin "3") (pinfunction "~{RI}_3") (pintype "input"))
    )
    (net (code "87") (name "unconnected-(IC7-~{RTS}-Pad32)") (class "Default")
      (node (ref "IC7") (pin "32") (pinfunction "~{RTS}_32") (pintype "output"))
    )
    (net (code "88") (name "unconnected-(M.2-M1-32-PadP$32)") (class "Default")
      (node (ref "M.2-M1") (pin "P$32") (pinfunction "32_P$32") (pintype "bidirectional"))
    )
    (net (code "89") (name "unconnected-(M.2-M1-34-PadP$34)") (class "Default")
      (node (ref "M.2-M1") (pin "P$34") (pinfunction "34_P$34") (pintype "bidirectional"))
    )
    (net (code "90") (name "unconnected-(M.2-M1-35-PadP$35)") (class "Default")
      (node (ref "M.2-M1") (pin "P$35") (pinfunction "35_P$35") (pintype "bidirectional"))
    )
    (net (code "91") (name "unconnected-(M.2-M1-36-PadP$36)") (class "Default")
      (node (ref "M.2-M1") (pin "P$36") (pinfunction "36_P$36") (pintype "bidirectional"))
    )
    (net (code "92") (name "unconnected-(M.2-M1-37-PadP$37)") (class "Default")
      (node (ref "M.2-M1") (pin "P$37") (pinfunction "37_P$37") (pintype "bidirectional"))
    )
    (net (code "93") (name "unconnected-(M.2-M1-38-PadP$38)") (class "Default")
      (node (ref "M.2-M1") (pin "P$38") (pinfunction "38_P$38") (pintype "bidirectional"))
    )
    (net (code "94") (name "unconnected-(M.2-M1-39-PadP$39)") (class "Default")
      (node (ref "M.2-M1") (pin "P$39") (pinfunction "39_P$39") (pintype "bidirectional"))
    )
    (net (code "95") (name "unconnected-(M.2-M1-40-PadP$40)") (class "Default")
      (node (ref "M.2-M1") (pin "P$40") (pinfunction "40_P$40") (pintype "bidirectional"))
    )
    (net (code "96") (name "unconnected-(M.2-M1-41-PadP$41)") (class "Default")
      (node (ref "M.2-M1") (pin "P$41") (pinfunction "41_P$41") (pintype "bidirectional"))
    )
    (net (code "97") (name "unconnected-(M.2-M1-42-PadP$42)") (class "Default")
      (node (ref "M.2-M1") (pin "P$42") (pinfunction "42_P$42") (pintype "bidirectional"))
    )
    (net (code "98") (name "unconnected-(M.2-M1-43-PadP$43)") (class "Default")
      (node (ref "M.2-M1") (pin "P$43") (pinfunction "43_P$43") (pintype "bidirectional"))
    )
    (net (code "99") (name "unconnected-(M.2-M1-44-PadP$44)") (class "Default")
      (node (ref "M.2-M1") (pin "P$44") (pinfunction "44_P$44") (pintype "bidirectional"))
    )
    (net (code "100") (name "unconnected-(M.2-M1-45-PadP$45)") (class "Default")
      (node (ref "M.2-M1") (pin "P$45") (pinfunction "45_P$45") (pintype "bidirectional"))
    )
    (net (code "101") (name "unconnected-(M.2-M1-46-PadP$46)") (class "Default")
      (node (ref "M.2-M1") (pin "P$46") (pinfunction "46_P$46") (pintype "bidirectional"))
    )
    (net (code "102") (name "unconnected-(M.2-M1-47-PadP$47)") (class "Default")
      (node (ref "M.2-M1") (pin "P$47") (pinfunction "47_P$47") (pintype "bidirectional"))
    )
    (net (code "103") (name "unconnected-(M.2-M1-48-PadP$48)") (class "Default")
      (node (ref "M.2-M1") (pin "P$48") (pinfunction "48_P$48") (pintype "bidirectional"))
    )
    (net (code "104") (name "unconnected-(M.2-M1-49-PadP$49)") (class "Default")
      (node (ref "M.2-M1") (pin "P$49") (pinfunction "49_P$49") (pintype "bidirectional"))
    )
    (net (code "105") (name "unconnected-(M.2-M1-50-PadP$50)") (class "Default")
      (node (ref "M.2-M1") (pin "P$50") (pinfunction "50_P$50") (pintype "bidirectional"))
    )
    (net (code "106") (name "~{QSPI_SS}") (class "Default")
      (node (ref "IC3") (pin "C2") (pinfunction "~{CS}_C2") (pintype "bidirectional"))
      (node (ref "IC4") (pin "56") (pinfunction "QSPI_SS_N_56") (pintype "bidirectional"))
    )
  )
)
